# Timer-Ruler_CR2032_on_top.net
KiCad netlist of a schematic drawn in EAGLE
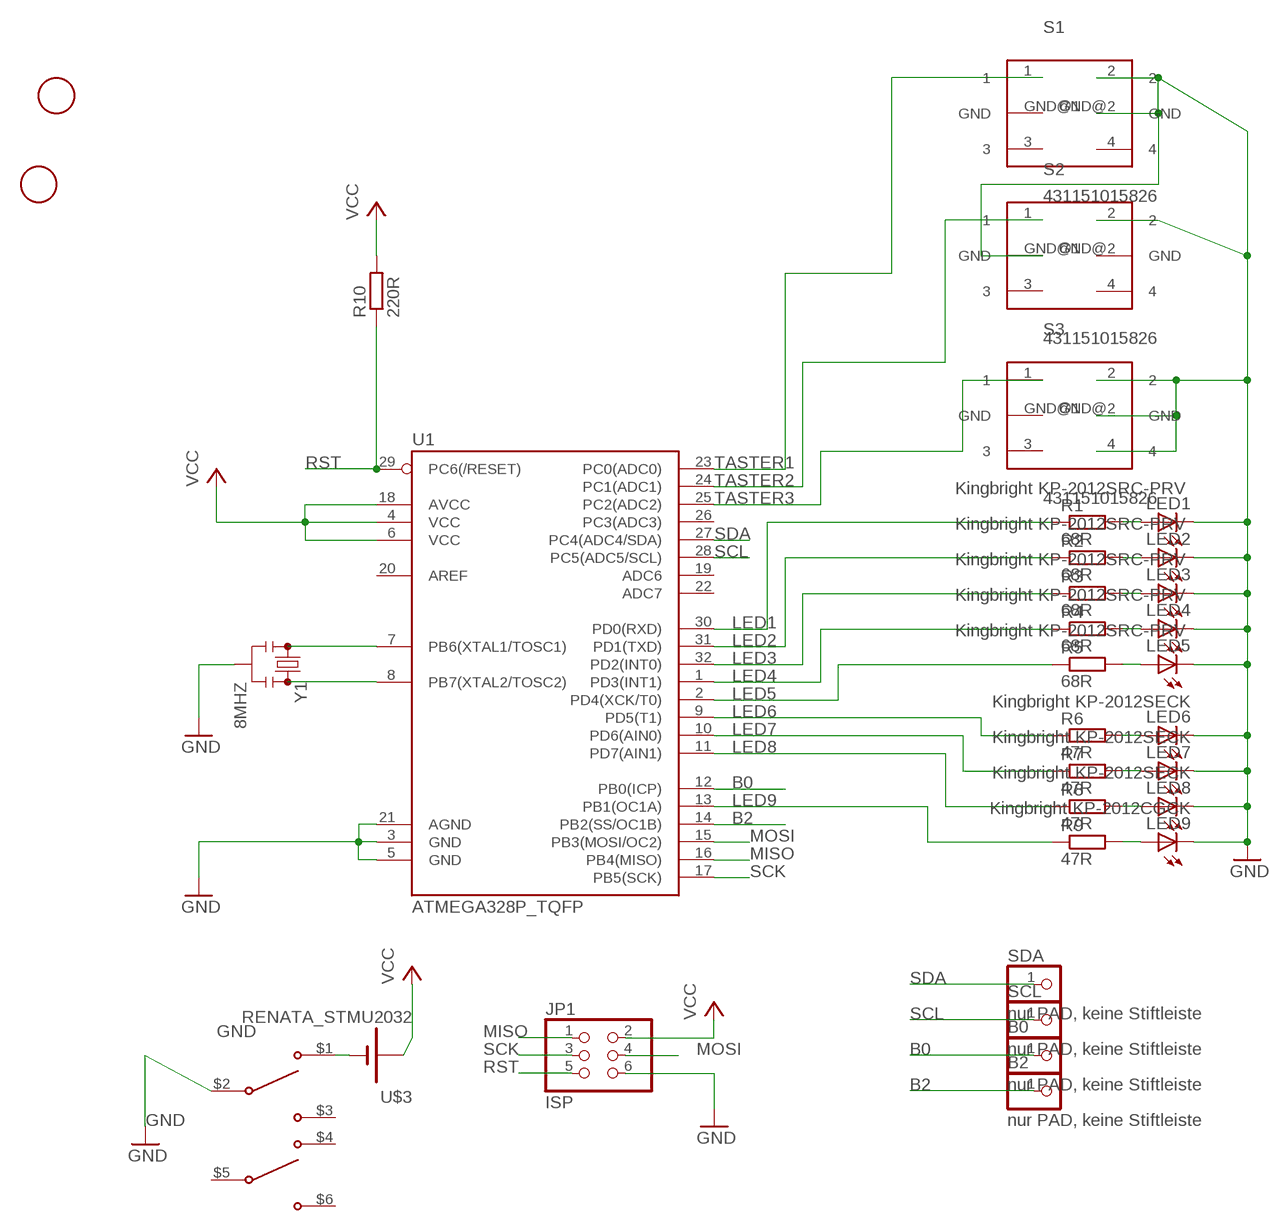
[diagram p0: schematic, sheet 1]

(export (version "E")
  (design (tool "Eeschema 10.0.6"))
  (components
    (comp (ref "B0")
      (value "nur PAD, keine Stiftleiste")
      (footprint "eagle-import:1X01")
      (libsource (lib "eagle-import") (part "PINHD-1X1"))
    )
    (comp (ref "B2")
      (value "nur PAD, keine Stiftleiste")
      (footprint "eagle-import:1X01")
      (libsource (lib "eagle-import") (part "PINHD-1X1"))
    )
    (comp (ref "JP1")
      (value "ISP")
      (footprint "eagle-import:2X03")
      (libsource (lib "eagle-import") (part "PINHD-2X3"))
    )
    (comp (ref "LED1")
      (value "Kingbright KP-2012SRC-PRV")
      (footprint "eagle-import:CHIP-LED0805")
      (libsource (lib "eagle-import") (part "LEDCHIP-LED0805"))
    )
    (comp (ref "LED2")
      (value "Kingbright KP-2012SRC-PRV")
      (footprint "eagle-import:CHIP-LED0805")
      (libsource (lib "eagle-import") (part "LEDCHIP-LED0805"))
    )
    (comp (ref "LED3")
      (value "Kingbright KP-2012SRC-PRV")
      (footprint "eagle-import:CHIP-LED0805")
      (libsource (lib "eagle-import") (part "LEDCHIP-LED0805"))
    )
    (comp (ref "LED4")
      (value "Kingbright KP-2012SRC-PRV")
      (footprint "eagle-import:CHIP-LED0805")
      (libsource (lib "eagle-import") (part "LEDCHIP-LED0805"))
    )
    (comp (ref "LED5")
      (value "Kingbright KP-2012SRC-PRV")
      (footprint "eagle-import:CHIP-LED0805")
      (libsource (lib "eagle-import") (part "LEDCHIP-LED0805"))
    )
    (comp (ref "LED6")
      (value "Kingbright KP-2012SECK")
      (footprint "eagle-import:CHIP-LED0805")
      (libsource (lib "eagle-import") (part "LEDCHIP-LED0805"))
    )
    (comp (ref "LED7")
      (value "Kingbright KP-2012SECK")
      (footprint "eagle-import:CHIP-LED0805")
      (libsource (lib "eagle-import") (part "LEDCHIP-LED0805"))
    )
    (comp (ref "LED8")
      (value "Kingbright KP-2012SECK")
      (footprint "eagle-import:CHIP-LED0805")
      (libsource (lib "eagle-import") (part "LEDCHIP-LED0805"))
    )
    (comp (ref "LED9")
      (value "Kingbright KP-2012CGCK")
      (footprint "eagle-import:CHIP-LED0805")
      (libsource (lib "eagle-import") (part "LEDCHIP-LED0805"))
    )
    (comp (ref "R1")
      (value "68R")
      (footprint "eagle-import:R0402")
      (libsource (lib "eagle-import") (part "R-EU_R0402"))
    )
    (comp (ref "R2")
      (value "68R")
      (footprint "eagle-import:R0402")
      (libsource (lib "eagle-import") (part "R-EU_R0402"))
    )
    (comp (ref "R3")
      (value "68R")
      (footprint "eagle-import:R0402")
      (libsource (lib "eagle-import") (part "R-EU_R0402"))
    )
    (comp (ref "R4")
      (value "68R")
      (footprint "eagle-import:R0402")
      (libsource (lib "eagle-import") (part "R-EU_R0402"))
    )
    (comp (ref "R5")
      (value "68R")
      (footprint "eagle-import:R0402")
      (libsource (lib "eagle-import") (part "R-EU_R0402"))
    )
    (comp (ref "R6")
      (value "47R")
      (footprint "eagle-import:R0402")
      (libsource (lib "eagle-import") (part "R-EU_R0402"))
    )
    (comp (ref "R7")
      (value "47R")
      (footprint "eagle-import:R0402")
      (libsource (lib "eagle-import") (part "R-EU_R0402"))
    )
    (comp (ref "R8")
      (value "47R")
      (footprint "eagle-import:R0402")
      (libsource (lib "eagle-import") (part "R-EU_R0402"))
    )
    (comp (ref "R9")
      (value "47R")
      (footprint "eagle-import:R0402")
      (libsource (lib "eagle-import") (part "R-EU_R0402"))
    )
    (comp (ref "R10")
      (value "220R")
      (footprint "eagle-import:R0402")
      (libsource (lib "eagle-import") (part "R-EU_R0402"))
    )
    (comp (ref "S1")
      (value "431151015826")
      (footprint "eagle-import:431181015816")
      (libsource (lib "eagle-import") (part "431151015826"))
    )
    (comp (ref "S2")
      (value "431151015826")
      (footprint "eagle-import:431181015816")
      (libsource (lib "eagle-import") (part "431151015826"))
    )
    (comp (ref "S3")
      (value "431151015826")
      (footprint "eagle-import:431181015816")
      (libsource (lib "eagle-import") (part "431151015826"))
    )
    (comp (ref "SCL")
      (value "nur PAD, keine Stiftleiste")
      (footprint "eagle-import:1X01")
      (libsource (lib "eagle-import") (part "PINHD-1X1"))
    )
    (comp (ref "SDA")
      (value "nur PAD, keine Stiftleiste")
      (footprint "eagle-import:1X01")
      (libsource (lib "eagle-import") (part "PINHD-1X1"))
    )
    (comp (ref "U$1")
      (value "FIDUCIAL")
      (footprint "eagle-import:FIDUCIAL_1MM")
      (libsource (lib "eagle-import") (part "FIDUCIAL"))
    )
    (comp (ref "U$2")
      (value "FIDUCIAL")
      (footprint "eagle-import:FIDUCIAL_1MM")
      (libsource (lib "eagle-import") (part "FIDUCIAL"))
    )
    (comp (ref "U$3")
      (value "RENATA_STMU2032")
      (footprint "eagle-import:SMTU2032")
      (libsource (lib "eagle-import") (part "RENATA_STMU2032"))
    )
    (comp (ref "U$4")
      (value "C+K_AYZ0202AGRLC")
      (footprint "eagle-import:C+K_AYZ0202AGRLC")
      (libsource (lib "eagle-import") (part "C+K_AYZ0202AGRLC"))
    )
    (comp (ref "U1")
      (value "ATMEGA328P_TQFP")
      (footprint "eagle-import:TQFP32-08")
      (libsource (lib "eagle-import") (part "ATMEGA328P_TQFP"))
    )
    (comp (ref "Y1")
      (value "8MHZ")
      (footprint "eagle-import:RESONATOR-SMD")
      (libsource (lib "eagle-import") (part "RESONATOR8MHZ"))
    )
  )
  (nets
    (net (code "1") (name "/B0") (class "Default")
      (node (ref "B0") (pin "1") (pinfunction "1_1") (pintype "passive"))
      (node (ref "U1") (pin "12") (pinfunction "PB0(ICP)_12") (pintype "bidirectional"))
    )
    (net (code "2") (name "/B2") (class "Default")
      (node (ref "B2") (pin "1") (pinfunction "1_1") (pintype "passive"))
      (node (ref "U1") (pin "14") (pinfunction "PB2(SS/OC1B)_14") (pintype "bidirectional"))
    )
    (net (code "3") (name "/LED1") (class "Default")
      (node (ref "R1") (pin "1") (pinfunction "1_1") (pintype "passive"))
      (node (ref "U1") (pin "30") (pinfunction "PD0(RXD)_30") (pintype "bidirectional"))
    )
    (net (code "4") (name "/LED2") (class "Default")
      (node (ref "R2") (pin "1") (pinfunction "1_1") (pintype "passive"))
      (node (ref "U1") (pin "31") (pinfunction "PD1(TXD)_31") (pintype "bidirectional"))
    )
    (net (code "5") (name "/LED3") (class "Default")
      (node (ref "R3") (pin "1") (pinfunction "1_1") (pintype "passive"))
      (node (ref "U1") (pin "32") (pinfunction "PD2(INT0)_32") (pintype "bidirectional"))
    )
    (net (code "6") (name "/LED4") (class "Default")
      (node (ref "R4") (pin "1") (pinfunction "1_1") (pintype "passive"))
      (node (ref "U1") (pin "1") (pinfunction "PD3(INT1)_1") (pintype "bidirectional"))
    )
    (net (code "7") (name "/LED5") (class "Default")
      (node (ref "R5") (pin "1") (pinfunction "1_1") (pintype "passive"))
      (node (ref "U1") (pin "2") (pinfunction "PD4(XCK/T0)_2") (pintype "bidirectional"))
    )
    (net (code "8") (name "/LED6") (class "Default")
      (node (ref "R6") (pin "1") (pinfunction "1_1") (pintype "passive"))
      (node (ref "U1") (pin "9") (pinfunction "PD5(T1)_9") (pintype "bidirectional"))
    )
    (net (code "9") (name "/LED7") (class "Default")
      (node (ref "R7") (pin "1") (pinfunction "1_1") (pintype "passive"))
      (node (ref "U1") (pin "10") (pinfunction "PD6(AIN0)_10") (pintype "bidirectional"))
    )
    (net (code "10") (name "/LED8") (class "Default")
      (node (ref "R8") (pin "1") (pinfunction "1_1") (pintype "passive"))
      (node (ref "U1") (pin "11") (pinfunction "PD7(AIN1)_11") (pintype "bidirectional"))
    )
    (net (code "11") (name "/LED9") (class "Default")
      (node (ref "R9") (pin "1") (pinfunction "1_1") (pintype "passive"))
      (node (ref "U1") (pin "13") (pinfunction "PB1(OC1A)_13") (pintype "bidirectional"))
    )
    (net (code "12") (name "/MISO") (class "Default")
      (node (ref "JP1") (pin "1") (pinfunction "1_1") (pintype "passive"))
      (node (ref "U1") (pin "16") (pinfunction "PB4(MISO)_16") (pintype "bidirectional"))
    )
    (net (code "13") (name "/MOSI") (class "Default")
      (node (ref "JP1") (pin "4") (pinfunction "4_4") (pintype "passive"))
      (node (ref "U1") (pin "15") (pinfunction "PB3(MOSI/OC2)_15") (pintype "bidirectional"))
    )
    (net (code "14") (name "/RST") (class "Default")
      (node (ref "JP1") (pin "5") (pinfunction "5_5") (pintype "passive"))
      (node (ref "R10") (pin "1") (pinfunction "1_1") (pintype "passive"))
      (node (ref "U1") (pin "29") (pinfunction "PC6(/RESET)_29") (pintype "bidirectional"))
    )
    (net (code "15") (name "/SCK") (class "Default")
      (node (ref "JP1") (pin "3") (pinfunction "3_3") (pintype "passive"))
      (node (ref "U1") (pin "17") (pinfunction "PB5(SCK)_17") (pintype "bidirectional"))
    )
    (net (code "16") (name "/SCL") (class "Default")
      (node (ref "SCL") (pin "1") (pinfunction "1_1") (pintype "passive"))
      (node (ref "U1") (pin "28") (pinfunction "PC5(ADC5/SCL)_28") (pintype "bidirectional"))
    )
    (net (code "17") (name "/SDA") (class "Default")
      (node (ref "SDA") (pin "1") (pinfunction "1_1") (pintype "passive"))
      (node (ref "U1") (pin "27") (pinfunction "PC4(ADC4/SDA)_27") (pintype "bidirectional"))
    )
    (net (code "18") (name "/TASTER1") (class "Default")
      (node (ref "S1") (pin "1") (pinfunction "1_1") (pintype "bidirectional"))
      (node (ref "U1") (pin "23") (pinfunction "PC0(ADC0)_23") (pintype "bidirectional"))
    )
    (net (code "19") (name "/TASTER2") (class "Default")
      (node (ref "S2") (pin "1") (pinfunction "1_1") (pintype "bidirectional"))
      (node (ref "U1") (pin "24") (pinfunction "PC1(ADC1)_24") (pintype "bidirectional"))
    )
    (net (code "20") (name "/TASTER3") (class "Default")
      (node (ref "S3") (pin "1") (pinfunction "1_1") (pintype "bidirectional"))
      (node (ref "U1") (pin "25") (pinfunction "PC2(ADC2)_25") (pintype "bidirectional"))
    )
    (net (code "21") (name "GND") (class "Default")
      (node (ref "JP1") (pin "6") (pinfunction "6_6") (pintype "passive"))
      (node (ref "LED1") (pin "C") (pinfunction "C_C") (pintype "passive"))
      (node (ref "LED2") (pin "C") (pinfunction "C_C") (pintype "passive"))
      (node (ref "LED3") (pin "C") (pinfunction "C_C") (pintype "passive"))
      (node (ref "LED4") (pin "C") (pinfunction "C_C") (pintype "passive"))
      (node (ref "LED5") (pin "C") (pinfunction "C_C") (pintype "passive"))
      (node (ref "LED6") (pin "C") (pinfunction "C_C") (pintype "passive"))
      (node (ref "LED7") (pin "C") (pinfunction "C_C") (pintype "passive"))
      (node (ref "LED8") (pin "C") (pinfunction "C_C") (pintype "passive"))
      (node (ref "LED9") (pin "C") (pinfunction "C_C") (pintype "passive"))
      (node (ref "S1") (pin "2") (pinfunction "2_2") (pintype "bidirectional"))
      (node (ref "S1") (pin "GND@2") (pinfunction "GND_GND@2") (pintype "bidirectional"))
      (node (ref "S2") (pin "2") (pinfunction "2_2") (pintype "bidirectional"))
      (node (ref "S2") (pin "GND@1") (pinfunction "GND_GND@1") (pintype "bidirectional"))
      (node (ref "S3") (pin "2") (pinfunction "2_2") (pintype "bidirectional"))
      (node (ref "S3") (pin "4") (pinfunction "4_4") (pintype "bidirectional"))
      (node (ref "S3") (pin "GND@2") (pinfunction "GND_GND@2") (pintype "bidirectional"))
      (node (ref "U$4") (pin "$2") (pinfunction "2_$2") (pintype "bidirectional"))
      (node (ref "U1") (pin "21") (pinfunction "AGND_21") (pintype "bidirectional"))
      (node (ref "U1") (pin "3") (pinfunction "GND_3") (pintype "bidirectional"))
      (node (ref "U1") (pin "5") (pinfunction "GND_5") (pintype "bidirectional"))
      (node (ref "Y1") (pin "2") (pinfunction "2_2") (pintype "passive"))
    )
    (net (code "22") (name "Net-(LED1-PadA)") (class "Default")
      (node (ref "LED1") (pin "A") (pinfunction "A_A") (pintype "passive"))
      (node (ref "R1") (pin "2") (pinfunction "2_2") (pintype "passive"))
    )
    (net (code "23") (name "Net-(LED2-PadA)") (class "Default")
      (node (ref "LED2") (pin "A") (pinfunction "A_A") (pintype "passive"))
      (node (ref "R2") (pin "2") (pinfunction "2_2") (pintype "passive"))
    )
    (net (code "24") (name "Net-(LED3-PadA)") (class "Default")
      (node (ref "LED3") (pin "A") (pinfunction "A_A") (pintype "passive"))
      (node (ref "R3") (pin "2") (pinfunction "2_2") (pintype "passive"))
    )
    (net (code "25") (name "Net-(LED4-PadA)") (class "Default")
      (node (ref "LED4") (pin "A") (pinfunction "A_A") (pintype "passive"))
      (node (ref "R4") (pin "2") (pinfunction "2_2") (pintype "passive"))
    )
    (net (code "26") (name "Net-(LED5-PadA)") (class "Default")
      (node (ref "LED5") (pin "A") (pinfunction "A_A") (pintype "passive"))
      (node (ref "R5") (pin "2") (pinfunction "2_2") (pintype "passive"))
    )
    (net (code "27") (name "Net-(LED6-PadA)") (class "Default")
      (node (ref "LED6") (pin "A") (pinfunction "A_A") (pintype "passive"))
      (node (ref "R6") (pin "2") (pinfunction "2_2") (pintype "passive"))
    )
    (net (code "28") (name "Net-(LED7-PadA)") (class "Default")
      (node (ref "LED7") (pin "A") (pinfunction "A_A") (pintype "passive"))
      (node (ref "R7") (pin "2") (pinfunction "2_2") (pintype "passive"))
    )
    (net (code "29") (name "Net-(LED8-PadA)") (class "Default")
      (node (ref "LED8") (pin "A") (pinfunction "A_A") (pintype "passive"))
      (node (ref "R8") (pin "2") (pinfunction "2_2") (pintype "passive"))
    )
    (net (code "30") (name "Net-(LED9-PadA)") (class "Default")
      (node (ref "LED9") (pin "A") (pinfunction "A_A") (pintype "passive"))
      (node (ref "R9") (pin "2") (pinfunction "2_2") (pintype "passive"))
    )
    (net (code "31") (name "Net-(U$4-1)") (class "Default")
      (node (ref "U$3") (pin "-") (pinfunction "-_-") (pintype "power_in"))
      (node (ref "U$4") (pin "$1") (pinfunction "1_$1") (pintype "bidirectional"))
    )
    (net (code "32") (name "Net-(U1-PB6(XTAL1{slash}TOSC1))") (class "Default")
      (node (ref "U1") (pin "7") (pinfunction "PB6(XTAL1/TOSC1)_7") (pintype "bidirectional"))
      (node (ref "Y1") (pin "1") (pinfunction "1_1") (pintype "passive"))
    )
    (net (code "33") (name "Net-(U1-PB7(XTAL2{slash}TOSC2))") (class "Default")
      (node (ref "U1") (pin "8") (pinfunction "PB7(XTAL2/TOSC2)_8") (pintype "bidirectional"))
      (node (ref "Y1") (pin "3") (pinfunction "3_3") (pintype "passive"))
    )
    (net (code "34") (name "VCC") (class "Default")
      (node (ref "JP1") (pin "2") (pinfunction "2_2") (pintype "passive"))
      (node (ref "R10") (pin "2") (pinfunction "2_2") (pintype "passive"))
      (node (ref "U$3") (pin "+") (pinfunction "+_+") (pintype "power_in"))
      (node (ref "U1") (pin "18") (pinfunction "AVCC_18") (pintype "bidirectional"))
      (node (ref "U1") (pin "4") (pinfunction "VCC_4") (pintype "bidirectional"))
      (node (ref "U1") (pin "6") (pinfunction "VCC_6") (pintype "bidirectional"))
    )
    (net (code "35") (name "unconnected-(S1-GND-PadGND@1)") (class "Default")
      (node (ref "S1") (pin "GND@1") (pinfunction "GND_GND@1") (pintype "bidirectional"))
    )
    (net (code "36") (name "unconnected-(S1-Pad3)") (class "Default")
      (node (ref "S1") (pin "3") (pinfunction "3_3") (pintype "bidirectional"))
    )
    (net (code "37") (name "unconnected-(S1-Pad4)") (class "Default")
      (node (ref "S1") (pin "4") (pinfunction "4_4") (pintype "bidirectional"))
    )
    (net (code "38") (name "unconnected-(S2-GND-PadGND@2)") (class "Default")
      (node (ref "S2") (pin "GND@2") (pinfunction "GND_GND@2") (pintype "bidirectional"))
    )
    (net (code "39") (name "unconnected-(S2-Pad3)") (class "Default")
      (node (ref "S2") (pin "3") (pinfunction "3_3") (pintype "bidirectional"))
    )
    (net (code "40") (name "unconnected-(S2-Pad4)") (class "Default")
      (node (ref "S2") (pin "4") (pinfunction "4_4") (pintype "bidirectional"))
    )
    (net (code "41") (name "unconnected-(S3-GND-PadGND@1)") (class "Default")
      (node (ref "S3") (pin "GND@1") (pinfunction "GND_GND@1") (pintype "bidirectional"))
    )
    (net (code "42") (name "unconnected-(S3-Pad3)") (class "Default")
      (node (ref "S3") (pin "3") (pinfunction "3_3") (pintype "bidirectional"))
    )
    (net (code "43") (name "unconnected-(U$4-3-Pad$3)") (class "Default")
      (node (ref "U$4") (pin "$3") (pinfunction "3_$3") (pintype "bidirectional"))
    )
    (net (code "44") (name "unconnected-(U$4-4-Pad$4)") (class "Default")
      (node (ref "U$4") (pin "$4") (pinfunction "4_$4") (pintype "bidirectional"))
    )
    (net (code "45") (name "unconnected-(U$4-5-Pad$5)") (class "Default")
      (node (ref "U$4") (pin "$5") (pinfunction "5_$5") (pintype "bidirectional"))
    )
    (net (code "46") (name "unconnected-(U$4-6-Pad$6)") (class "Default")
      (node (ref "U$4") (pin "$6") (pinfunction "6_$6") (pintype "bidirectional"))
    )
    (net (code "47") (name "unconnected-(U1-ADC6-Pad19)") (class "Default")
      (node (ref "U1") (pin "19") (pinfunction "ADC6_19") (pintype "bidirectional"))
    )
    (net (code "48") (name "unconnected-(U1-ADC7-Pad22)") (class "Default")
      (node (ref "U1") (pin "22") (pinfunction "ADC7_22") (pintype "bidirectional"))
    )
    (net (code "49") (name "unconnected-(U1-AREF-Pad20)") (class "Default")
      (node (ref "U1") (pin "20") (pinfunction "AREF_20") (pintype "bidirectional"))
    )
    (net (code "50") (name "unconnected-(U1-PC3(ADC3)-Pad26)") (class "Default")
      (node (ref "U1") (pin "26") (pinfunction "PC3(ADC3)_26") (pintype "bidirectional"))
    )
  )
)
